# DIGLITE.net
KiCad netlist of a schematic drawn in Altium Designer
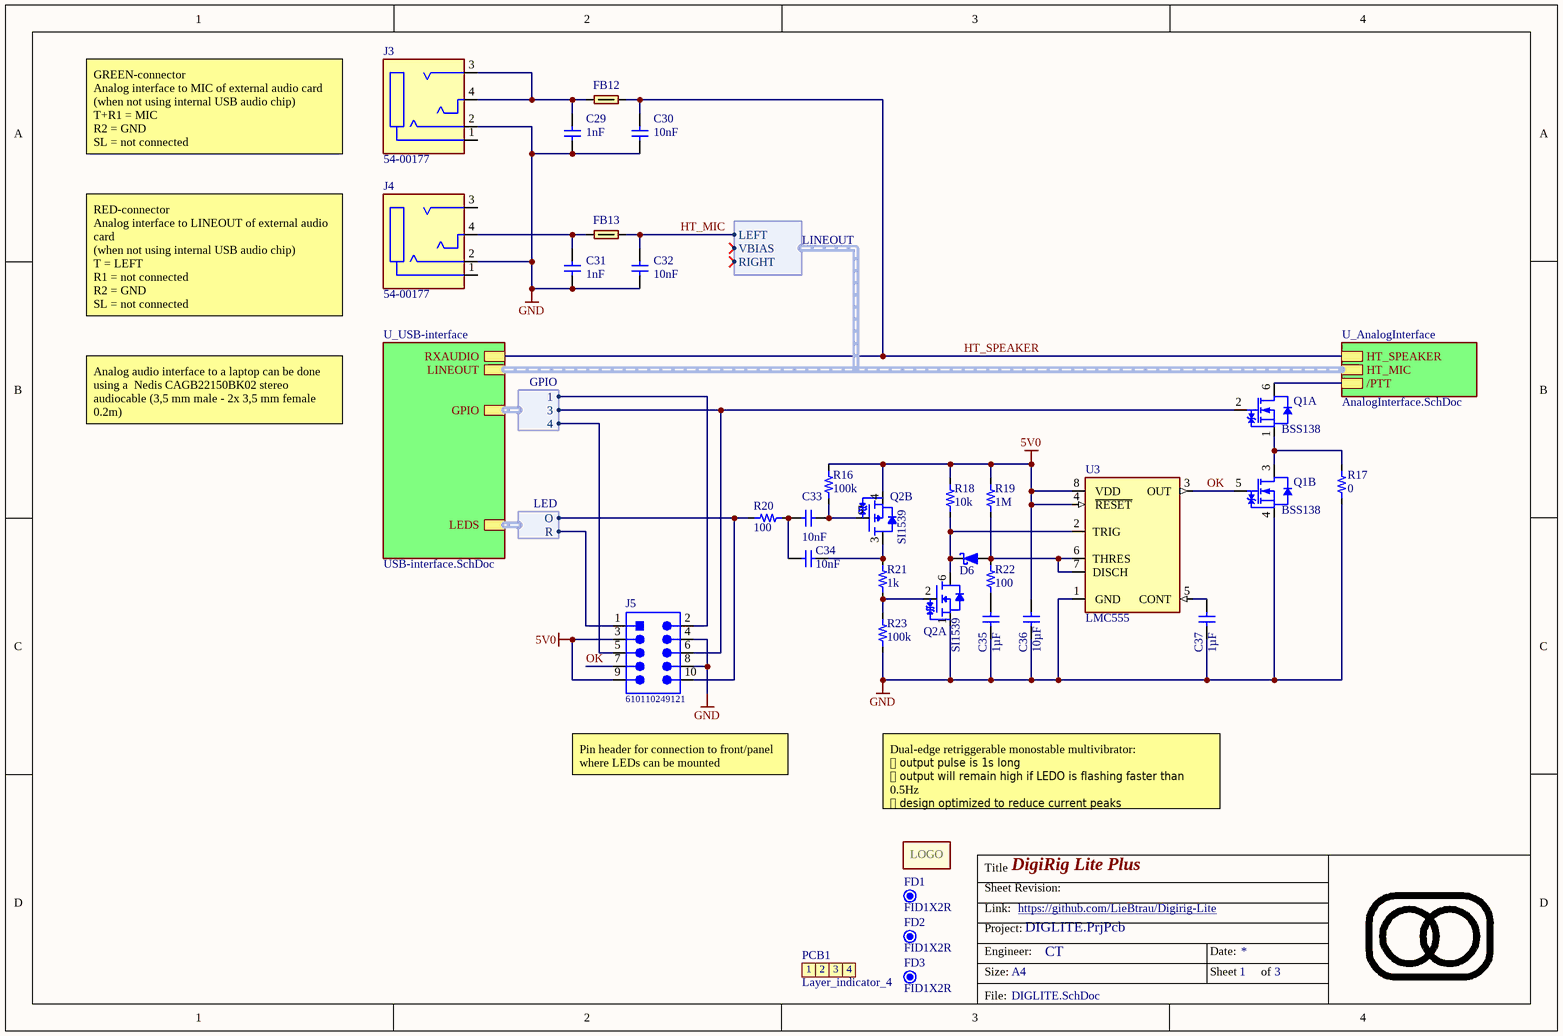
[diagram p0: DIGLITE.SchDoc]

(export (version "E")
  (design (tool "Eeschema 10.0.6"))
  (components
    (comp (ref "C29")
      (value "1nF")
      (footprint "0603-C-N")
      (description "Capacitor MLCC, General Purpose, size 0603, C0G, 1 nF, +/-5%, 50V")
      (fields (field (name "TOLERANCE") "5%") (field (name "JLCPCB PART #") "C340644"))
      (libsource (lib "7c7 Engineering") (part "CAP-NP-2"))
    )
    (comp (ref "C30")
      (value "10nF")
      (footprint "0603-C-N")
      (description "Multilayer Ceramic Capacitor, Grm Series, 0.01 F, 5%, C0g / Np0, 50 V, 0603 [1608 Metric]")
      (fields (field (name "VOLTAGE") "50V") (field (name "TOLERANCE") "5%"))
      (libsource (lib "7c7 Engineering") (part "CAP-NP-2"))
    )
    (comp (ref "C31")
      (value "1nF")
      (footprint "0603-C-N")
      (description "Capacitor MLCC, General Purpose, size 0603, C0G, 1 nF, +/-5%, 50V")
      (fields (field (name "TOLERANCE") "5%") (field (name "JLCPCB PART #") "C340644"))
      (libsource (lib "7c7 Engineering") (part "CAP-NP-2"))
    )
    (comp (ref "C32")
      (value "10nF")
      (footprint "0603-C-N")
      (description "Multilayer Ceramic Capacitor, Grm Series, 0.01 F, 5%, C0g / Np0, 50 V, 0603 [1608 Metric]")
      (fields (field (name "VOLTAGE") "50V") (field (name "TOLERANCE") "5%"))
      (libsource (lib "7c7 Engineering") (part "CAP-NP-2"))
    )
    (comp (ref "C33")
      (value "10nF")
      (footprint "0603-C-N")
      (description "Multilayer Ceramic Capacitor, Grm Series, 0.01 F, 5%, C0g / Np0, 50 V, 0603 [1608 Metric]")
      (fields (field (name "VOLTAGE") "50V") (field (name "TOLERANCE") "5%"))
      (libsource (lib "7c7 Engineering") (part "CAP-NP-2"))
    )
    (comp (ref "C34")
      (value "10nF")
      (footprint "0603-C-N")
      (description "Multilayer Ceramic Capacitor, Grm Series, 0.01 F, 5%, C0g / Np0, 50 V, 0603 [1608 Metric]")
      (fields (field (name "VOLTAGE") "50V") (field (name "TOLERANCE") "5%"))
      (libsource (lib "7c7 Engineering") (part "CAP-NP-2"))
    )
    (comp (ref "C35")
      (value "1µF")
      (footprint "0603-C-N")
      (description "Capacitor MLCC, General Purpose, size 0603, X7R, 1µF, +/-10%, 16V")
      (fields (field (name "TOLERANCE") "10%") (field (name "JLCPCB PART #") "C15849"))
      (libsource (lib "7c7 Engineering") (part "CAP-NP-2"))
    )
    (comp (ref "C36")
      (value "10µF")
      (footprint "WCAP-CSGP_1210_L3.2W2.5H2.5")
      (description "WCAP-CSGP Multilayer Ceramic Chip Capacitor, General Purpose, size 1210, X7R, 10µF, 50VDC")
      (fields (field (name "TOLERANCE") "10%") (field (name "JLCPCB PART #") "C77102"))
      (libsource (lib "7c7 Engineering") (part "CAP-NP-2"))
    )
    (comp (ref "C37")
      (value "1µF")
      (footprint "0603-C-N")
      (description "Capacitor MLCC, General Purpose, size 0603, X7R, 1µF, +/-10%, 16V")
      (fields (field (name "TOLERANCE") "10%") (field (name "JLCPCB PART #") "C15849"))
      (libsource (lib "7c7 Engineering") (part "CAP-NP-2"))
    )
    (comp (ref "D6")
      (value "RB521SM-30T2R")
      (footprint "FP-SOD523-MFG")
      (description "RB521SM Series 30 V 200 mA Surface Mount Schottky Barrier Diode -SOD-523 (SC-79)")
      (fields (field (name "JLCPCB PART #") "C727120"))
      (libsource (lib "7c7 Engineering") (part "DIODE-SKY-2"))
    )
    (comp (ref "FB12")
      (value "742792662")
      (footprint "0603-FB-N")
      (description "WE-CBF SMT EMI Suppression Ferrite Bead, size 0603, 1000O, 0.83A")
      (fields (field (name "JLCPCB PART #") "C180490") (field (name "MANUFACTURER") "Wurth Elektronik"))
      (libsource (lib "7c7 Engineering") (part "IND_BEAD"))
    )
    (comp (ref "FB13")
      (value "742792662")
      (footprint "0603-FB-N")
      (description "WE-CBF SMT EMI Suppression Ferrite Bead, size 0603, 1000O, 0.83A")
      (fields (field (name "JLCPCB PART #") "C180490") (field (name "MANUFACTURER") "Wurth Elektronik"))
      (libsource (lib "7c7 Engineering") (part "IND_BEAD"))
    )
    (comp (ref "FD1")
      (value "FID1X2R")
      (footprint "FID1X2R")
      (description "Fiducial - Round 1x2mm")
      (libsource (lib "7c7 Engineering") (part "CMP-00134-2"))
    )
    (comp (ref "FD2")
      (value "FID1X2R")
      (footprint "FID1X2R")
      (description "Fiducial - Round 1x2mm")
      (libsource (lib "7c7 Engineering") (part "CMP-00134-2"))
    )
    (comp (ref "FD3")
      (value "FID1X2R")
      (footprint "FID1X2R")
      (description "Fiducial - Round 1x2mm")
      (libsource (lib "7c7 Engineering") (part "CMP-00134-2"))
    )
    (comp (ref "J3")
      (value "54-00177")
      (footprint "54-00177-Footprint-1")
      (description "Conn Jack 4 Cond 3.5MM SMD R/a")
      (fields (field (name "JLCPCB PART #") "C7507452"))
      (libsource (lib "7c7 Engineering") (part "CN_AUDIO_JACK_TRRS_NO_SWITCH"))
    )
    (comp (ref "J4")
      (value "54-00177")
      (footprint "54-00177-Footprint-1")
      (description "Conn Jack 4 Cond 3.5MM SMD R/a")
      (fields (field (name "JLCPCB PART #") "C7507452"))
      (libsource (lib "7c7 Engineering") (part "CN_AUDIO_JACK_TRRS_NO_SWITCH"))
    )
    (comp (ref "J5")
      (value "610110249121")
      (footprint "610110249121")
      (description "WR-PHD Pin Header, SMT, pitch 2.54mm, Dual Row, Angled, 10p")
      (fields (field (name "MANUFACTURER") "Wurth Elektronik") (field (name "JLCPCB PART #") "C5149355"))
      (libsource (lib "7c7 Engineering") (part "Symbol"))
    )
    (comp (ref "M1")
      (value "Logo")
      (footprint "LOGO_9x6mm")
      (libsource (lib "Integrated_Library_LieBtrau") (part "Logo"))
    )
    (comp (ref "PCB1")
      (value "Layer_indicator_4")
      (footprint "LayerId_4L_4x1.5mm")
      (description "Layer indicator for 4 layers")
      (libsource (lib "7c7 Engineering") (part "Layer_indicator_4-Symbol-1"))
    )
    (comp (ref "Q1")
      (value "BSS138")
      (footprint "SOT-363-N")
      (description "Transistor MOSFET Array Dual N-CH 60V 320mA 6-Pin TSSOP T/R")
      (fields (field (name "JLCPCB PART #") "C154900") (field (name "PAGE PART #") "TBSS138PS"))
      (libsource (lib "7c7 Engineering") (part "2NMOS"))
    )
    (comp (ref "Q2")
      (value "SI1539")
      (footprint "SOT-363-N")
      (description "Trans Mosfet N/p-ch 30V 0.7A/0.4A 6-PIN SC-70 T/r / Mosfet N/p-ch 30V SOT363")
      (fields (field (name "JLCPCB PART #") "C141530") (field (name "Comment") "SI1539CDL-T1-GE3"))
      (libsource (lib "7c7 Engineering") (part "CMOS"))
    )
    (comp (ref "R16")
      (value "100k")
      (footprint "0603-R-N")
      (description "Chip Resistor, Thick Film, General Purpose, 0603, 100mW, 50V, 100 kOhm, +/-1%")
      (fields (field (name "TOLERANCE") "1%") (field (name "JLCPCB PART #") "C25803"))
      (libsource (lib "7c7 Engineering") (part "RES"))
    )
    (comp (ref "R17")
      (value "0")
      (footprint "0603-R-N")
      (description "Chip Jumper, Thick Film, Jumper, 0603, 100mW, 1A, 0 Ohm, <50 mOhm")
      (fields (field (name "FLIR PART #") "YRES0E-1") (field (name "TOLERANCE") "50 mOhm"))
      (libsource (lib "7c7 Engineering") (part "RES"))
    )
    (comp (ref "R18")
      (value "10k")
      (footprint "0603-R-N")
      (description "Chip Resistor, Thick Film, General Purpose, 0603, 100mW, 50V, 10 kOhm, +/-1%")
      (fields (field (name "FLIR PART #") "YRES10K-1") (field (name "PAGE PART #") "ROQF1002"))
      (libsource (lib "7c7 Engineering") (part "RES"))
    )
    (comp (ref "R19")
      (value "1M")
      (footprint "0603-R-N")
      (description "Chip Resistor, Thick Film, General Purpose, 0603, 100mW, 50V, 1 MOhm, +/-1%")
      (fields (field (name "TOLERANCE") "1%") (field (name "JLCPCB PART #") "C22935"))
      (libsource (lib "7c7 Engineering") (part "RES"))
    )
    (comp (ref "R20")
      (value "100")
      (footprint "0603-R-N")
      (description "Chip Resistor, Thick Film, General Purpose, 0603, 63mW, 50V, 100 Ohm, +/-1%")
      (fields (field (name "JLCPCB PART #") "C22775") (field (name "TOLERANCE") "1%"))
      (libsource (lib "7c7 Engineering") (part "RES"))
    )
    (comp (ref "R21")
      (value "1k")
      (footprint "0603-R-N")
      (description "Chip Resistor, Thick Film, General Purpose, 0603, 100mW, 50V, 1 kOhm, +/-1%")
      (fields (field (name "JLCPCB PART #") "C21190") (field (name "TOLERANCE") "1%"))
      (libsource (lib "7c7 Engineering") (part "RES"))
    )
    (comp (ref "R22")
      (value "100")
      (footprint "0603-R-N")
      (description "Chip Resistor, Thick Film, General Purpose, 0603, 63mW, 50V, 100 Ohm, +/-1%")
      (fields (field (name "JLCPCB PART #") "C22775") (field (name "TOLERANCE") "1%"))
      (libsource (lib "7c7 Engineering") (part "RES"))
    )
    (comp (ref "R23")
      (value "100k")
      (footprint "0603-R-N")
      (description "Chip Resistor, Thick Film, General Purpose, 0603, 100mW, 50V, 100 kOhm, +/-1%")
      (fields (field (name "TOLERANCE") "1%") (field (name "JLCPCB PART #") "C25803"))
      (libsource (lib "7c7 Engineering") (part "RES"))
    )
    (comp (ref "U3")
      (value "LMC555")
      (footprint "VSSOP8")
      (description "World’s smallest 555 timer with low power, high accuracy and a Fmax of 3MHz 8-VSSOP -40 to 85")
      (fields (field (name "JLCPCB PART #") "C5160090") (field (name "Comment") "LMC555CMM/NOPB"))
      (libsource (lib "7c7 Engineering") (part "555-Timer"))
    )
  )
  (nets
    (net (code "4") (name "/1") (class "Default")
      (node (ref "J5") (pin "2") (pinfunction "2_2") (pintype "passive"))
    )
    (net (code "5") (name "/3") (class "Default")
      (node (ref "J5") (pin "6") (pinfunction "6_6") (pintype "passive"))
      (node (ref "Q1") (pin "2") (pinfunction "G_2") (pintype "passive"))
    )
    (net (code "6") (name "/4") (class "Default")
      (node (ref "J5") (pin "5") (pinfunction "5_5") (pintype "passive"))
    )
    (net (code "7") (name "/HT_MIC") (class "Default")
      (node (ref "C32") (pin "1") (pinfunction "1_1") (pintype "passive"))
      (node (ref "FB13") (pin "2") (pinfunction "2_2") (pintype "passive"))
    )
    (net (code "8") (name "/HT_SPEAKER") (class "Default")
      (node (ref "C30") (pin "1") (pinfunction "1_1") (pintype "passive"))
      (node (ref "FB12") (pin "2") (pinfunction "2_2") (pintype "passive"))
    )
    (net (code "9") (name "/O") (class "Default")
      (node (ref "J5") (pin "10") (pinfunction "10_10") (pintype "passive"))
      (node (ref "R20") (pin "2") (pinfunction "2_2") (pintype "passive"))
    )
    (net (code "10") (name "/OK") (class "Default")
      (node (ref "J5") (pin "7") (pinfunction "7_7") (pintype "passive"))
      (node (ref "Q1") (pin "5") (pinfunction "G_5") (pintype "passive"))
      (node (ref "U3") (pin "3") (pinfunction "OUT_3") (pintype "output"))
    )
    (net (code "11") (name "/R") (class "Default")
      (node (ref "J5") (pin "1") (pinfunction "1_1") (pintype "passive"))
    )
    (net (code "15") (name "/{slash}PTT") (class "Default")
      (node (ref "Q1") (pin "6") (pinfunction "D_6") (pintype "passive"))
    )
    (net (code "16") (name "5V0") (class "Default")
      (node (ref "C36") (pin "2") (pinfunction "2_2") (pintype "passive"))
      (node (ref "J5") (pin "3") (pinfunction "3_3") (pintype "passive"))
      (node (ref "J5") (pin "9") (pinfunction "9_9") (pintype "passive"))
      (node (ref "Q2") (pin "4") (pinfunction "S_4") (pintype "passive"))
      (node (ref "R16") (pin "2") (pinfunction "2_2") (pintype "passive"))
      (node (ref "R18") (pin "2") (pinfunction "2_2") (pintype "passive"))
      (node (ref "R19") (pin "2") (pinfunction "2_2") (pintype "passive"))
      (node (ref "U3") (pin "4") (pinfunction "~{RESET}_4") (pintype "input"))
      (node (ref "U3") (pin "8") (pinfunction "VDD_8") (pintype "power_in"))
    )
    (net (code "17") (name "GND") (class "Default")
      (node (ref "C29") (pin "2") (pinfunction "2_2") (pintype "passive"))
      (node (ref "C30") (pin "2") (pinfunction "2_2") (pintype "passive"))
      (node (ref "C31") (pin "2") (pinfunction "2_2") (pintype "passive"))
      (node (ref "C32") (pin "2") (pinfunction "2_2") (pintype "passive"))
      (node (ref "C35") (pin "1") (pinfunction "1_1") (pintype "passive"))
      (node (ref "C36") (pin "1") (pinfunction "1_1") (pintype "passive"))
      (node (ref "C37") (pin "1") (pinfunction "1_1") (pintype "passive"))
      (node (ref "J3") (pin "2") (pinfunction "2_2") (pintype "passive"))
      (node (ref "J4") (pin "2") (pinfunction "2_2") (pintype "passive"))
      (node (ref "J5") (pin "4") (pinfunction "4_4") (pintype "passive"))
      (node (ref "J5") (pin "8") (pinfunction "8_8") (pintype "passive"))
      (node (ref "Q1") (pin "4") (pinfunction "S_4") (pintype "passive"))
      (node (ref "Q2") (pin "1") (pinfunction "S_1") (pintype "passive"))
      (node (ref "R17") (pin "1") (pinfunction "1_1") (pintype "passive"))
      (node (ref "R23") (pin "1") (pinfunction "1_1") (pintype "passive"))
      (node (ref "U3") (pin "1") (pinfunction "GND_1") (pintype "power_in"))
    )
    (net (code "18") (name "Net-(C29-Pad1)") (class "Default")
      (node (ref "C29") (pin "1") (pinfunction "1_1") (pintype "passive"))
      (node (ref "FB12") (pin "1") (pinfunction "1_1") (pintype "passive"))
      (node (ref "J3") (pin "3") (pinfunction "3_3") (pintype "passive"))
      (node (ref "J3") (pin "4") (pinfunction "4_4") (pintype "passive"))
    )
    (net (code "19") (name "Net-(C31-Pad1)") (class "Default")
      (node (ref "C31") (pin "1") (pinfunction "1_1") (pintype "passive"))
      (node (ref "FB13") (pin "1") (pinfunction "1_1") (pintype "passive"))
      (node (ref "J4") (pin "4") (pinfunction "4_4") (pintype "passive"))
    )
    (net (code "20") (name "Net-(C33-Pad1)") (class "Default")
      (node (ref "C33") (pin "1") (pinfunction "1_1") (pintype "passive"))
      (node (ref "C34") (pin "1") (pinfunction "1_1") (pintype "passive"))
      (node (ref "R20") (pin "1") (pinfunction "1_1") (pintype "passive"))
    )
    (net (code "21") (name "Net-(C35-Pad2)") (class "Default")
      (node (ref "C35") (pin "2") (pinfunction "2_2") (pintype "passive"))
      (node (ref "R22") (pin "1") (pinfunction "1_1") (pintype "passive"))
    )
    (net (code "22") (name "Net-(D6-A)") (class "Default")
      (node (ref "D6") (pin "2") (pinfunction "A_2") (pintype "passive"))
      (node (ref "R19") (pin "1") (pinfunction "1_1") (pintype "passive"))
      (node (ref "R22") (pin "2") (pinfunction "2_2") (pintype "passive"))
      (node (ref "U3") (pin "6") (pinfunction "THRES_6") (pintype "passive"))
      (node (ref "U3") (pin "7") (pinfunction "DISCH_7") (pintype "open_collector"))
    )
    (net (code "23") (name "Net-(D6-K)") (class "Default")
      (node (ref "D6") (pin "1") (pinfunction "K_1") (pintype "passive"))
      (node (ref "Q2") (pin "6") (pinfunction "D_6") (pintype "passive"))
      (node (ref "R18") (pin "1") (pinfunction "1_1") (pintype "passive"))
      (node (ref "U3") (pin "2") (pinfunction "TRIG_2") (pintype "passive"))
    )
    (net (code "24") (name "Net-(Q1A-S)") (class "Default")
      (node (ref "Q1") (pin "1") (pinfunction "S_1") (pintype "passive"))
      (node (ref "Q1") (pin "3") (pinfunction "D_3") (pintype "passive"))
      (node (ref "R17") (pin "2") (pinfunction "2_2") (pintype "passive"))
    )
    (net (code "25") (name "Net-(Q2A-G)") (class "Default")
      (node (ref "Q2") (pin "2") (pinfunction "G_2") (pintype "passive"))
      (node (ref "R21") (pin "2") (pinfunction "2_2") (pintype "passive"))
      (node (ref "R23") (pin "2") (pinfunction "2_2") (pintype "passive"))
    )
    (net (code "26") (name "Net-(Q2B-D)") (class "Default")
      (node (ref "C34") (pin "2") (pinfunction "2_2") (pintype "passive"))
      (node (ref "Q2") (pin "3") (pinfunction "D_3") (pintype "passive"))
      (node (ref "R21") (pin "1") (pinfunction "1_1") (pintype "passive"))
    )
    (net (code "27") (name "Net-(Q2B-G)") (class "Default")
      (node (ref "C33") (pin "2") (pinfunction "2_2") (pintype "passive"))
      (node (ref "Q2") (pin "5") (pinfunction "G_5") (pintype "passive"))
      (node (ref "R16") (pin "1") (pinfunction "1_1") (pintype "passive"))
    )
    (net (code "28") (name "Net-(U3-CONT)") (class "Default")
      (node (ref "C37") (pin "2") (pinfunction "2_2") (pintype "passive"))
      (node (ref "U3") (pin "5") (pinfunction "CONT_5") (pintype "input"))
    )
    (net (code "29") (name "unconnected-(J3-Pad1)") (class "Default")
      (node (ref "J3") (pin "1") (pinfunction "1_1") (pintype "passive"))
    )
    (net (code "30") (name "unconnected-(J4-Pad1)") (class "Default")
      (node (ref "J4") (pin "1") (pinfunction "1_1") (pintype "passive"))
    )
    (net (code "31") (name "unconnected-(J4-Pad3)") (class "Default")
      (node (ref "J4") (pin "3") (pinfunction "3_3") (pintype "passive"))
    )
  )
)
